# Bluetooth_testr.net
KiCad netlist of a schematic drawn in EAGLE
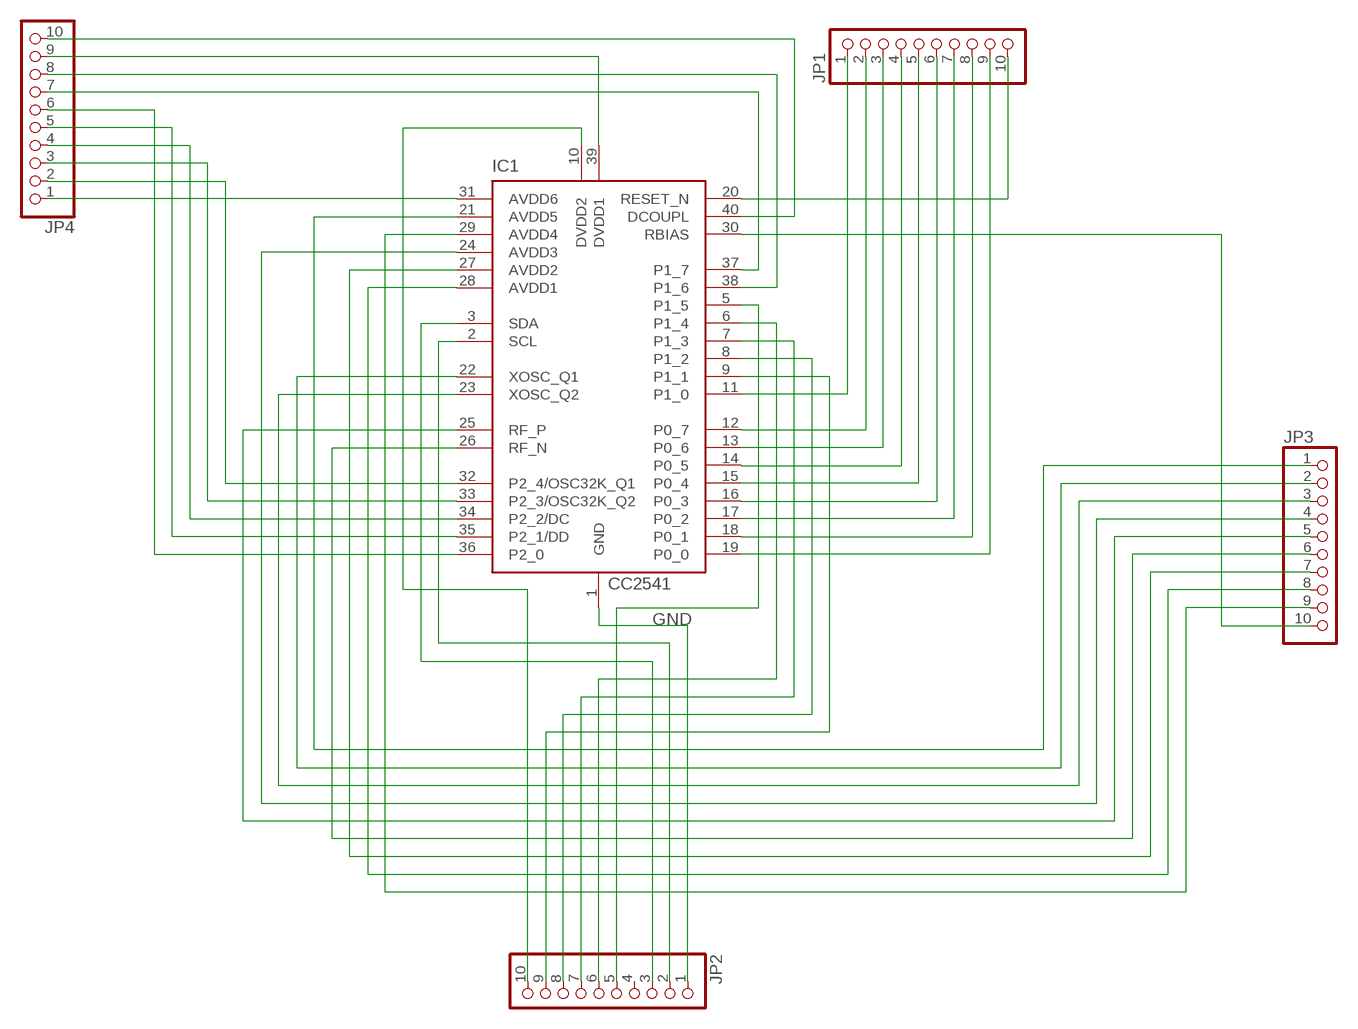
[diagram p0: schematic, sheet 1]

(export (version "E")
  (design (tool "Eeschema 10.0.6"))
  (components
    (comp (ref "IC1")
      (value "CC2541")
      (footprint "eagle-import:QFN40-6X6")
      (libsource (lib "eagle-import") (part "CC2541"))
    )
    (comp (ref "JP1")
      (value "PINHD-1X10")
      (footprint "eagle-import:1X10")
      (libsource (lib "eagle-import") (part "PINHD-1X10"))
    )
    (comp (ref "JP2")
      (value "PINHD-1X10")
      (footprint "eagle-import:1X10")
      (libsource (lib "eagle-import") (part "PINHD-1X10"))
    )
    (comp (ref "JP3")
      (value "PINHD-1X10")
      (footprint "eagle-import:1X10")
      (libsource (lib "eagle-import") (part "PINHD-1X10"))
    )
    (comp (ref "JP4")
      (value "PINHD-1X10")
      (footprint "eagle-import:1X10")
      (libsource (lib "eagle-import") (part "PINHD-1X10"))
    )
  )
  (nets
    (net (code "1") (name "/GND") (class "Default")
      (node (ref "IC1") (pin "1") (pinfunction "GND_1") (pintype "power_in"))
      (node (ref "JP2") (pin "1") (pinfunction "1_1") (pintype "passive"))
    )
    (net (code "2") (name "Net-(IC1-AVDD1)") (class "Default")
      (node (ref "IC1") (pin "28") (pinfunction "AVDD1_28") (pintype "power_in"))
      (node (ref "JP3") (pin "8") (pinfunction "8_8") (pintype "passive"))
    )
    (net (code "3") (name "Net-(IC1-AVDD2)") (class "Default")
      (node (ref "IC1") (pin "27") (pinfunction "AVDD2_27") (pintype "power_in"))
      (node (ref "JP3") (pin "7") (pinfunction "7_7") (pintype "passive"))
    )
    (net (code "4") (name "Net-(IC1-AVDD3)") (class "Default")
      (node (ref "IC1") (pin "24") (pinfunction "AVDD3_24") (pintype "power_in"))
      (node (ref "JP3") (pin "4") (pinfunction "4_4") (pintype "passive"))
    )
    (net (code "5") (name "Net-(IC1-AVDD4)") (class "Default")
      (node (ref "IC1") (pin "29") (pinfunction "AVDD4_29") (pintype "power_in"))
      (node (ref "JP3") (pin "9") (pinfunction "9_9") (pintype "passive"))
    )
    (net (code "6") (name "Net-(IC1-AVDD5)") (class "Default")
      (node (ref "IC1") (pin "21") (pinfunction "AVDD5_21") (pintype "power_in"))
      (node (ref "JP3") (pin "1") (pinfunction "1_1") (pintype "passive"))
    )
    (net (code "7") (name "Net-(IC1-AVDD6)") (class "Default")
      (node (ref "IC1") (pin "31") (pinfunction "AVDD6_31") (pintype "power_in"))
      (node (ref "JP4") (pin "1") (pinfunction "1_1") (pintype "passive"))
    )
    (net (code "8") (name "Net-(IC1-DCOUPL)") (class "Default")
      (node (ref "IC1") (pin "40") (pinfunction "DCOUPL_40") (pintype "power_in"))
      (node (ref "JP4") (pin "10") (pinfunction "10_10") (pintype "passive"))
    )
    (net (code "9") (name "Net-(IC1-DVDD1)") (class "Default")
      (node (ref "IC1") (pin "39") (pinfunction "DVDD1_39") (pintype "power_in"))
      (node (ref "JP4") (pin "9") (pinfunction "9_9") (pintype "passive"))
    )
    (net (code "10") (name "Net-(IC1-DVDD2)") (class "Default")
      (node (ref "IC1") (pin "10") (pinfunction "DVDD2_10") (pintype "power_in"))
      (node (ref "JP2") (pin "10") (pinfunction "10_10") (pintype "passive"))
    )
    (net (code "11") (name "Net-(IC1-P0_0)") (class "Default")
      (node (ref "IC1") (pin "19") (pinfunction "P0_0_19") (pintype "bidirectional"))
      (node (ref "JP1") (pin "9") (pinfunction "9_9") (pintype "passive"))
    )
    (net (code "12") (name "Net-(IC1-P0_1)") (class "Default")
      (node (ref "IC1") (pin "18") (pinfunction "P0_1_18") (pintype "bidirectional"))
      (node (ref "JP1") (pin "8") (pinfunction "8_8") (pintype "passive"))
    )
    (net (code "13") (name "Net-(IC1-P0_2)") (class "Default")
      (node (ref "IC1") (pin "17") (pinfunction "P0_2_17") (pintype "bidirectional"))
      (node (ref "JP1") (pin "7") (pinfunction "7_7") (pintype "passive"))
    )
    (net (code "14") (name "Net-(IC1-P0_3)") (class "Default")
      (node (ref "IC1") (pin "16") (pinfunction "P0_3_16") (pintype "bidirectional"))
      (node (ref "JP1") (pin "6") (pinfunction "6_6") (pintype "passive"))
    )
    (net (code "15") (name "Net-(IC1-P0_4)") (class "Default")
      (node (ref "IC1") (pin "15") (pinfunction "P0_4_15") (pintype "bidirectional"))
      (node (ref "JP1") (pin "5") (pinfunction "5_5") (pintype "passive"))
    )
    (net (code "16") (name "Net-(IC1-P0_5)") (class "Default")
      (node (ref "IC1") (pin "14") (pinfunction "P0_5_14") (pintype "bidirectional"))
      (node (ref "JP1") (pin "4") (pinfunction "4_4") (pintype "passive"))
    )
    (net (code "17") (name "Net-(IC1-P0_6)") (class "Default")
      (node (ref "IC1") (pin "13") (pinfunction "P0_6_13") (pintype "bidirectional"))
      (node (ref "JP1") (pin "3") (pinfunction "3_3") (pintype "passive"))
    )
    (net (code "18") (name "Net-(IC1-P0_7)") (class "Default")
      (node (ref "IC1") (pin "12") (pinfunction "P0_7_12") (pintype "bidirectional"))
      (node (ref "JP1") (pin "2") (pinfunction "2_2") (pintype "passive"))
    )
    (net (code "19") (name "Net-(IC1-P1_0)") (class "Default")
      (node (ref "IC1") (pin "11") (pinfunction "P1_0_11") (pintype "bidirectional"))
      (node (ref "JP1") (pin "1") (pinfunction "1_1") (pintype "passive"))
    )
    (net (code "20") (name "Net-(IC1-P1_1)") (class "Default")
      (node (ref "IC1") (pin "9") (pinfunction "P1_1_9") (pintype "bidirectional"))
      (node (ref "JP2") (pin "9") (pinfunction "9_9") (pintype "passive"))
    )
    (net (code "21") (name "Net-(IC1-P1_2)") (class "Default")
      (node (ref "IC1") (pin "8") (pinfunction "P1_2_8") (pintype "bidirectional"))
      (node (ref "JP2") (pin "8") (pinfunction "8_8") (pintype "passive"))
    )
    (net (code "22") (name "Net-(IC1-P1_3)") (class "Default")
      (node (ref "IC1") (pin "7") (pinfunction "P1_3_7") (pintype "bidirectional"))
      (node (ref "JP2") (pin "7") (pinfunction "7_7") (pintype "passive"))
    )
    (net (code "23") (name "Net-(IC1-P1_4)") (class "Default")
      (node (ref "IC1") (pin "6") (pinfunction "P1_4_6") (pintype "bidirectional"))
      (node (ref "JP2") (pin "6") (pinfunction "6_6") (pintype "passive"))
    )
    (net (code "24") (name "Net-(IC1-P1_5)") (class "Default")
      (node (ref "IC1") (pin "5") (pinfunction "P1_5_5") (pintype "bidirectional"))
      (node (ref "JP2") (pin "5") (pinfunction "5_5") (pintype "passive"))
    )
    (net (code "25") (name "Net-(IC1-P1_6)") (class "Default")
      (node (ref "IC1") (pin "38") (pinfunction "P1_6_38") (pintype "bidirectional"))
      (node (ref "JP4") (pin "8") (pinfunction "8_8") (pintype "passive"))
    )
    (net (code "26") (name "Net-(IC1-P1_7)") (class "Default")
      (node (ref "IC1") (pin "37") (pinfunction "P1_7_37") (pintype "bidirectional"))
      (node (ref "JP4") (pin "7") (pinfunction "7_7") (pintype "passive"))
    )
    (net (code "27") (name "Net-(IC1-P2_0)") (class "Default")
      (node (ref "IC1") (pin "36") (pinfunction "P2_0_36") (pintype "bidirectional"))
      (node (ref "JP4") (pin "6") (pinfunction "6_6") (pintype "passive"))
    )
    (net (code "28") (name "Net-(IC1-P2_1{slash}DD)") (class "Default")
      (node (ref "IC1") (pin "35") (pinfunction "P2_1/DD_35") (pintype "bidirectional"))
      (node (ref "JP4") (pin "5") (pinfunction "5_5") (pintype "passive"))
    )
    (net (code "29") (name "Net-(IC1-P2_2{slash}DC)") (class "Default")
      (node (ref "IC1") (pin "34") (pinfunction "P2_2/DC_34") (pintype "bidirectional"))
      (node (ref "JP4") (pin "4") (pinfunction "4_4") (pintype "passive"))
    )
    (net (code "30") (name "Net-(IC1-P2_3{slash}OSC32K_Q2)") (class "Default")
      (node (ref "IC1") (pin "33") (pinfunction "P2_3/OSC32K_Q2_33") (pintype "bidirectional"))
      (node (ref "JP4") (pin "3") (pinfunction "3_3") (pintype "passive"))
    )
    (net (code "31") (name "Net-(IC1-P2_4{slash}OSC32K_Q1)") (class "Default")
      (node (ref "IC1") (pin "32") (pinfunction "P2_4/OSC32K_Q1_32") (pintype "bidirectional"))
      (node (ref "JP4") (pin "2") (pinfunction "2_2") (pintype "passive"))
    )
    (net (code "32") (name "Net-(IC1-RBIAS)") (class "Default")
      (node (ref "IC1") (pin "30") (pinfunction "RBIAS_30") (pintype "bidirectional"))
      (node (ref "JP3") (pin "10") (pinfunction "10_10") (pintype "passive"))
    )
    (net (code "33") (name "Net-(IC1-RESET_N)") (class "Default")
      (node (ref "IC1") (pin "20") (pinfunction "RESET_N_20") (pintype "input"))
      (node (ref "JP1") (pin "10") (pinfunction "10_10") (pintype "passive"))
    )
    (net (code "34") (name "Net-(IC1-RF_N)") (class "Default")
      (node (ref "IC1") (pin "26") (pinfunction "RF_N_26") (pintype "bidirectional"))
      (node (ref "JP3") (pin "6") (pinfunction "6_6") (pintype "passive"))
    )
    (net (code "35") (name "Net-(IC1-RF_P)") (class "Default")
      (node (ref "IC1") (pin "25") (pinfunction "RF_P_25") (pintype "bidirectional"))
      (node (ref "JP3") (pin "5") (pinfunction "5_5") (pintype "passive"))
    )
    (net (code "36") (name "Net-(IC1-SCL)") (class "Default")
      (node (ref "IC1") (pin "2") (pinfunction "SCL_2") (pintype "bidirectional"))
      (node (ref "JP2") (pin "2") (pinfunction "2_2") (pintype "passive"))
    )
    (net (code "37") (name "Net-(IC1-SDA)") (class "Default")
      (node (ref "IC1") (pin "3") (pinfunction "SDA_3") (pintype "bidirectional"))
      (node (ref "JP2") (pin "3") (pinfunction "3_3") (pintype "passive"))
    )
    (net (code "38") (name "Net-(IC1-XOSC_Q1)") (class "Default")
      (node (ref "IC1") (pin "22") (pinfunction "XOSC_Q1_22") (pintype "bidirectional"))
      (node (ref "JP3") (pin "2") (pinfunction "2_2") (pintype "passive"))
    )
    (net (code "39") (name "Net-(IC1-XOSC_Q2)") (class "Default")
      (node (ref "IC1") (pin "23") (pinfunction "XOSC_Q2_23") (pintype "bidirectional"))
      (node (ref "JP3") (pin "3") (pinfunction "3_3") (pintype "passive"))
    )
    (net (code "40") (name "unconnected-(JP2-Pad4)") (class "Default")
      (node (ref "JP2") (pin "4") (pinfunction "4_4") (pintype "passive"))
    )
  )
)
